# VCALin.net
KiCad netlist of a schematic drawn in EAGLE
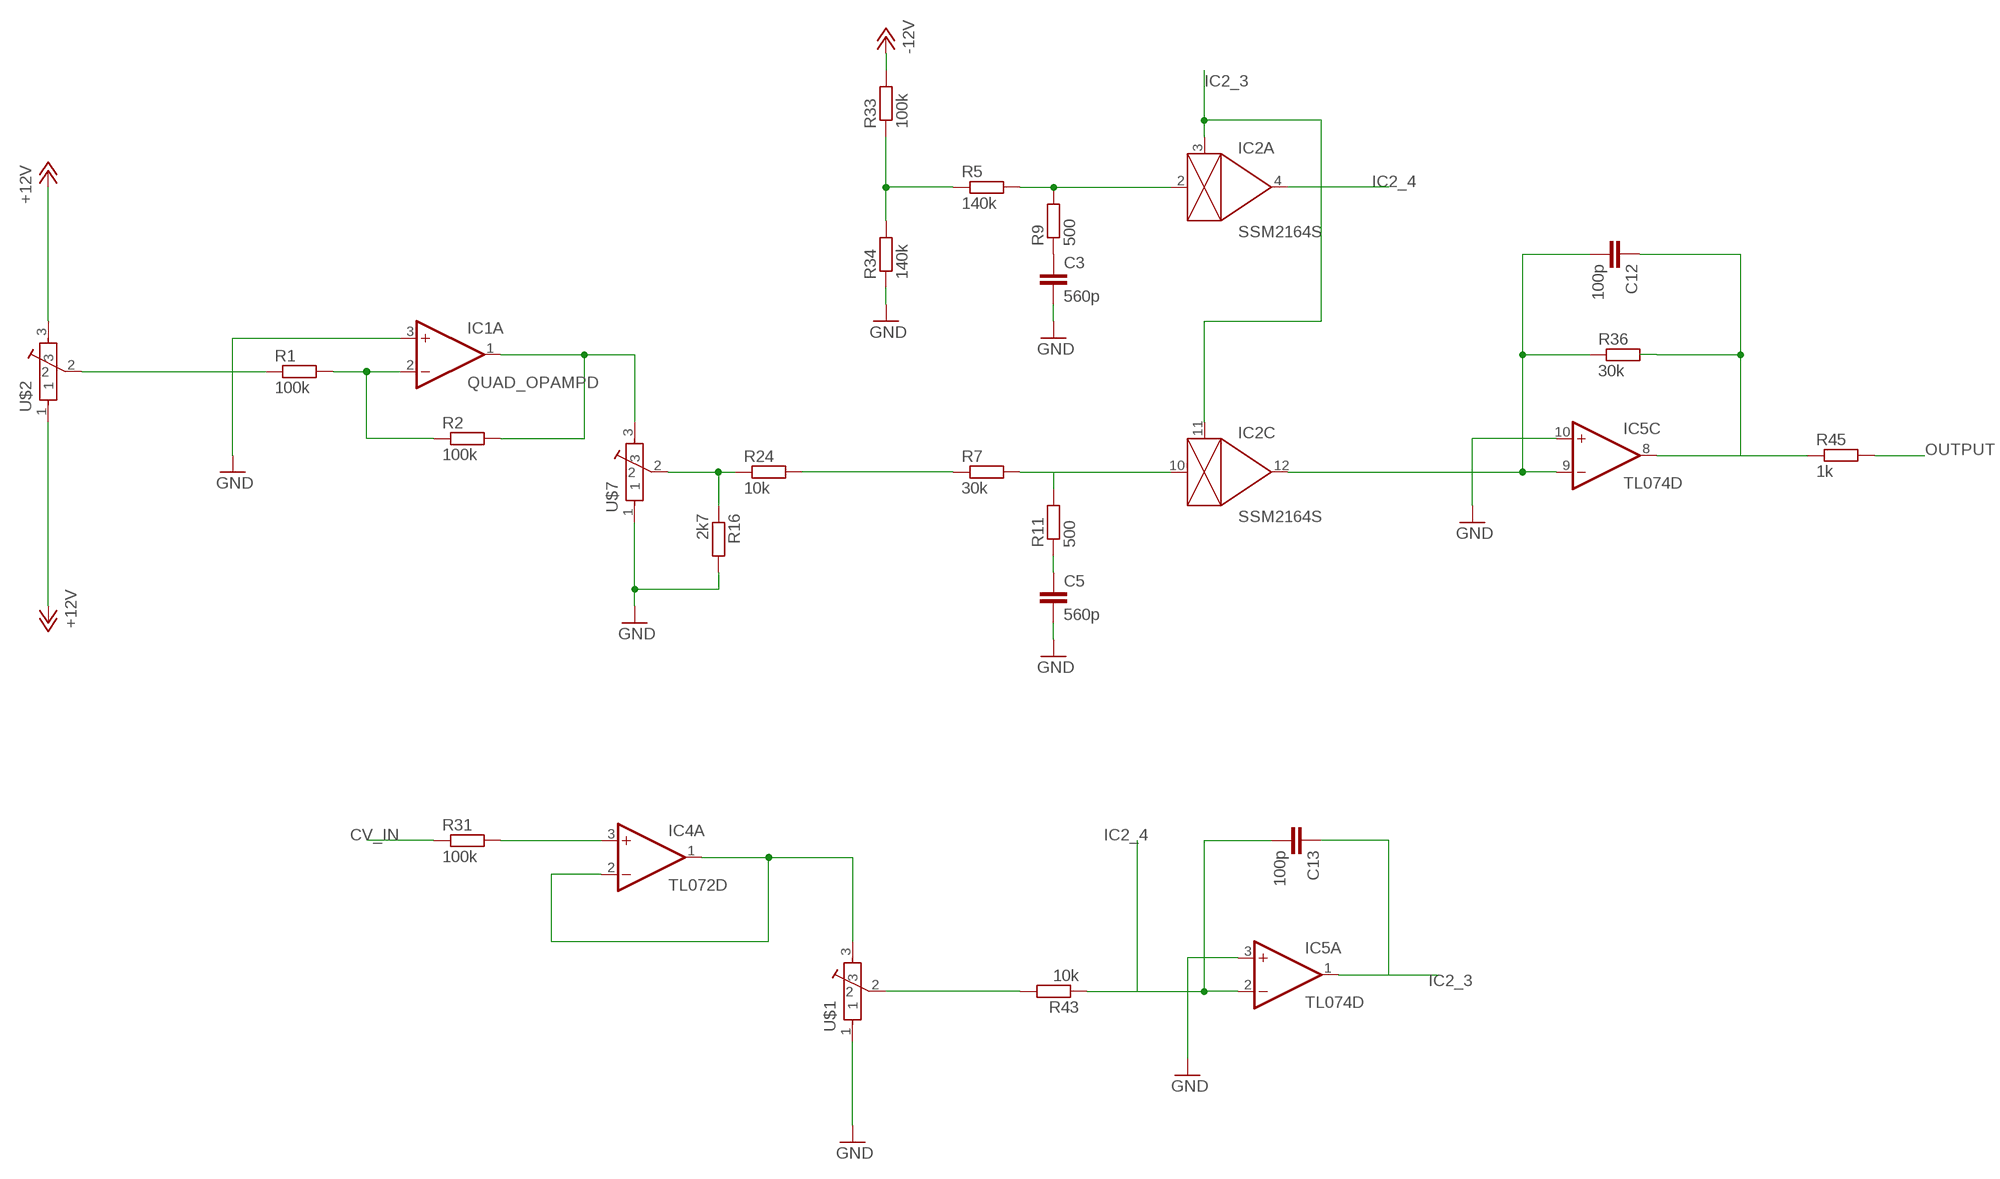
[diagram p0: schematic, sheet 1]

(export (version "E")
  (design (tool "Eeschema 10.0.6"))
  (components
    (comp (ref "C3")
      (value "560p")
      (footprint "eagle-import:C0603K")
      (libsource (lib "eagle-import") (part "C-EUC0603K"))
    )
    (comp (ref "C5")
      (value "560p")
      (footprint "eagle-import:C0603K")
      (libsource (lib "eagle-import") (part "C-EUC0603K"))
    )
    (comp (ref "C12")
      (value "100p")
      (footprint "eagle-import:C0603K")
      (libsource (lib "eagle-import") (part "C-EUC0603K"))
    )
    (comp (ref "C13")
      (value "100p")
      (footprint "eagle-import:C0603K")
      (libsource (lib "eagle-import") (part "C-EUC0603K"))
    )
    (comp (ref "IC1")
      (value "QUAD_OPAMPD")
      (footprint "eagle-import:SO14")
      (libsource (lib "eagle-import") (part "QUAD_OPAMPD"))
    )
    (comp (ref "IC2")
      (value "SSM2164S")
      (footprint "eagle-import:SOIC16N")
      (libsource (lib "eagle-import") (part "SSM2164S"))
    )
    (comp (ref "IC4")
      (value "TL072D")
      (footprint "eagle-import:SO08")
      (libsource (lib "eagle-import") (part "TL072D"))
    )
    (comp (ref "IC5")
      (value "TL074D")
      (footprint "eagle-import:SO14")
      (libsource (lib "eagle-import") (part "TL074D"))
    )
    (comp (ref "R1")
      (value "100k")
      (footprint "eagle-import:0603")
      (libsource (lib "eagle-import") (part "R-EU_0603"))
    )
    (comp (ref "R2")
      (value "100k")
      (footprint "eagle-import:0603")
      (libsource (lib "eagle-import") (part "R-EU_0603"))
    )
    (comp (ref "R5")
      (value "140k")
      (footprint "eagle-import:0603")
      (libsource (lib "eagle-import") (part "R-EU_0603"))
    )
    (comp (ref "R7")
      (value "30k")
      (footprint "eagle-import:0603")
      (libsource (lib "eagle-import") (part "R-EU_0603"))
    )
    (comp (ref "R9")
      (value "500")
      (footprint "eagle-import:0603")
      (libsource (lib "eagle-import") (part "R-EU_0603"))
    )
    (comp (ref "R11")
      (value "500")
      (footprint "eagle-import:0603")
      (libsource (lib "eagle-import") (part "R-EU_0603"))
    )
    (comp (ref "R16")
      (value "2k7")
      (footprint "eagle-import:0603")
      (libsource (lib "eagle-import") (part "R-EU_0603"))
    )
    (comp (ref "R24")
      (value "10k")
      (footprint "eagle-import:0603")
      (libsource (lib "eagle-import") (part "R-EU_0603"))
    )
    (comp (ref "R31")
      (value "100k")
      (footprint "eagle-import:0603")
      (libsource (lib "eagle-import") (part "R-EU_0603"))
    )
    (comp (ref "R33")
      (value "100k")
      (footprint "eagle-import:0603")
      (libsource (lib "eagle-import") (part "R-EU_0603"))
    )
    (comp (ref "R34")
      (value "140k")
      (footprint "eagle-import:0603")
      (libsource (lib "eagle-import") (part "R-EU_0603"))
    )
    (comp (ref "R36")
      (value "30k")
      (footprint "eagle-import:0603")
      (libsource (lib "eagle-import") (part "R-EU_0603"))
    )
    (comp (ref "R43")
      (value "10k")
      (footprint "eagle-import:0603")
      (libsource (lib "eagle-import") (part "R-EU_0603"))
    )
    (comp (ref "R45")
      (value "1k")
      (footprint "eagle-import:0603")
      (libsource (lib "eagle-import") (part "R-EU_0603"))
    )
    (comp (ref "U$1")
      (value "POT-ALPS-RK09L1140")
      (footprint "eagle-import:POT-ALPS-RK09L1140")
      (libsource (lib "eagle-import") (part "POT-ALPS-RK09L1140"))
    )
    (comp (ref "U$2")
      (value "POT-ALPS-RK09L1140")
      (footprint "eagle-import:POT-ALPS-RK09L1140")
      (libsource (lib "eagle-import") (part "POT-ALPS-RK09L1140"))
    )
    (comp (ref "U$7")
      (value "POT-ALPS-RK09L1140")
      (footprint "eagle-import:POT-ALPS-RK09L1140")
      (libsource (lib "eagle-import") (part "POT-ALPS-RK09L1140"))
    )
  )
  (nets
    (net (code "1") (name "+12V") (class "Default")
      (node (ref "U$2") (pin "1") (pinfunction "1_1") (pintype "bidirectional"))
      (node (ref "U$2") (pin "3") (pinfunction "3_3") (pintype "bidirectional"))
    )
    (net (code "2") (name "-12V") (class "Default")
      (node (ref "R33") (pin "2") (pinfunction "2_2") (pintype "passive"))
    )
    (net (code "3") (name "/CV_IN") (class "Default")
      (node (ref "R31") (pin "1") (pinfunction "1_1") (pintype "passive"))
    )
    (net (code "4") (name "/IC2_3") (class "Default")
      (node (ref "C13") (pin "1") (pinfunction "1_1") (pintype "passive"))
      (node (ref "IC2") (pin "11") (pinfunction "CTRL_11") (pintype "input"))
      (node (ref "IC2") (pin "3") (pinfunction "CTRL_3") (pintype "input"))
      (node (ref "IC5") (pin "1") (pinfunction "OUT_1") (pintype "output"))
    )
    (net (code "5") (name "/IC2_4") (class "Default")
      (node (ref "C13") (pin "2") (pinfunction "2_2") (pintype "passive"))
      (node (ref "IC2") (pin "4") (pinfunction "OUT_4") (pintype "output"))
      (node (ref "IC5") (pin "2") (pinfunction "-IN_2") (pintype "input"))
      (node (ref "R43") (pin "1") (pinfunction "1_1") (pintype "passive"))
    )
    (net (code "6") (name "/OUTPUT") (class "Default")
      (node (ref "R45") (pin "2") (pinfunction "2_2") (pintype "passive"))
    )
    (net (code "7") (name "GND") (class "Default")
      (node (ref "C3") (pin "2") (pinfunction "2_2") (pintype "passive"))
      (node (ref "C5") (pin "2") (pinfunction "2_2") (pintype "passive"))
      (node (ref "IC1") (pin "3") (pinfunction "+IN_3") (pintype "input"))
      (node (ref "IC5") (pin "10") (pinfunction "+IN_10") (pintype "input"))
      (node (ref "IC5") (pin "3") (pinfunction "+IN_3") (pintype "input"))
      (node (ref "R16") (pin "2") (pinfunction "2_2") (pintype "passive"))
      (node (ref "R34") (pin "1") (pinfunction "1_1") (pintype "passive"))
      (node (ref "U$1") (pin "1") (pinfunction "1_1") (pintype "bidirectional"))
      (node (ref "U$7") (pin "1") (pinfunction "1_1") (pintype "bidirectional"))
    )
    (net (code "8") (name "Net-(C3-Pad1)") (class "Default")
      (node (ref "C3") (pin "1") (pinfunction "1_1") (pintype "passive"))
      (node (ref "R9") (pin "1") (pinfunction "1_1") (pintype "passive"))
    )
    (net (code "9") (name "Net-(C5-Pad1)") (class "Default")
      (node (ref "C5") (pin "1") (pinfunction "1_1") (pintype "passive"))
      (node (ref "R11") (pin "1") (pinfunction "1_1") (pintype "passive"))
    )
    (net (code "10") (name "Net-(IC1A--IN)") (class "Default")
      (node (ref "IC1") (pin "2") (pinfunction "-IN_2") (pintype "input"))
      (node (ref "R1") (pin "2") (pinfunction "2_2") (pintype "passive"))
      (node (ref "R2") (pin "1") (pinfunction "1_1") (pintype "passive"))
    )
    (net (code "11") (name "Net-(IC1A-OUT)") (class "Default")
      (node (ref "IC1") (pin "1") (pinfunction "OUT_1") (pintype "output"))
      (node (ref "R2") (pin "2") (pinfunction "2_2") (pintype "passive"))
      (node (ref "U$7") (pin "3") (pinfunction "3_3") (pintype "bidirectional"))
    )
    (net (code "12") (name "Net-(IC2A-IN)") (class "Default")
      (node (ref "IC2") (pin "2") (pinfunction "IN_2") (pintype "input"))
      (node (ref "R5") (pin "2") (pinfunction "2_2") (pintype "passive"))
      (node (ref "R9") (pin "2") (pinfunction "2_2") (pintype "passive"))
    )
    (net (code "13") (name "Net-(IC2C-IN)") (class "Default")
      (node (ref "IC2") (pin "10") (pinfunction "IN_10") (pintype "input"))
      (node (ref "R11") (pin "2") (pinfunction "2_2") (pintype "passive"))
      (node (ref "R7") (pin "2") (pinfunction "2_2") (pintype "passive"))
    )
    (net (code "14") (name "Net-(IC2C-OUT)") (class "Default")
      (node (ref "C12") (pin "2") (pinfunction "2_2") (pintype "passive"))
      (node (ref "IC2") (pin "12") (pinfunction "OUT_12") (pintype "output"))
      (node (ref "IC5") (pin "9") (pinfunction "-IN_9") (pintype "input"))
      (node (ref "R36") (pin "1") (pinfunction "1_1") (pintype "passive"))
    )
    (net (code "15") (name "Net-(IC4A-+IN)") (class "Default")
      (node (ref "IC4") (pin "3") (pinfunction "+IN_3") (pintype "input"))
      (node (ref "R31") (pin "2") (pinfunction "2_2") (pintype "passive"))
    )
    (net (code "16") (name "Net-(IC4A--IN)") (class "Default")
      (node (ref "IC4") (pin "1") (pinfunction "OUT_1") (pintype "output"))
      (node (ref "IC4") (pin "2") (pinfunction "-IN_2") (pintype "input"))
      (node (ref "U$1") (pin "3") (pinfunction "3_3") (pintype "bidirectional"))
    )
    (net (code "17") (name "Net-(IC5C-OUT)") (class "Default")
      (node (ref "C12") (pin "1") (pinfunction "1_1") (pintype "passive"))
      (node (ref "IC5") (pin "8") (pinfunction "OUT_8") (pintype "output"))
      (node (ref "R36") (pin "2") (pinfunction "2_2") (pintype "passive"))
      (node (ref "R45") (pin "1") (pinfunction "1_1") (pintype "passive"))
    )
    (net (code "18") (name "Net-(R1-Pad1)") (class "Default")
      (node (ref "R1") (pin "1") (pinfunction "1_1") (pintype "passive"))
      (node (ref "U$2") (pin "2") (pinfunction "2_2") (pintype "bidirectional"))
    )
    (net (code "19") (name "Net-(R16-Pad1)") (class "Default")
      (node (ref "R16") (pin "1") (pinfunction "1_1") (pintype "passive"))
      (node (ref "R24") (pin "1") (pinfunction "1_1") (pintype "passive"))
      (node (ref "U$7") (pin "2") (pinfunction "2_2") (pintype "bidirectional"))
    )
    (net (code "20") (name "Net-(R24-Pad2)") (class "Default")
      (node (ref "R24") (pin "2") (pinfunction "2_2") (pintype "passive"))
      (node (ref "R7") (pin "1") (pinfunction "1_1") (pintype "passive"))
    )
    (net (code "21") (name "Net-(R33-Pad1)") (class "Default")
      (node (ref "R33") (pin "1") (pinfunction "1_1") (pintype "passive"))
      (node (ref "R34") (pin "2") (pinfunction "2_2") (pintype "passive"))
      (node (ref "R5") (pin "1") (pinfunction "1_1") (pintype "passive"))
    )
    (net (code "22") (name "Net-(R43-Pad2)") (class "Default")
      (node (ref "R43") (pin "2") (pinfunction "2_2") (pintype "passive"))
      (node (ref "U$1") (pin "2") (pinfunction "2_2") (pintype "bidirectional"))
    )
  )
)
